# charge_pump.net
KiCad netlist of a schematic drawn in Altium Designer
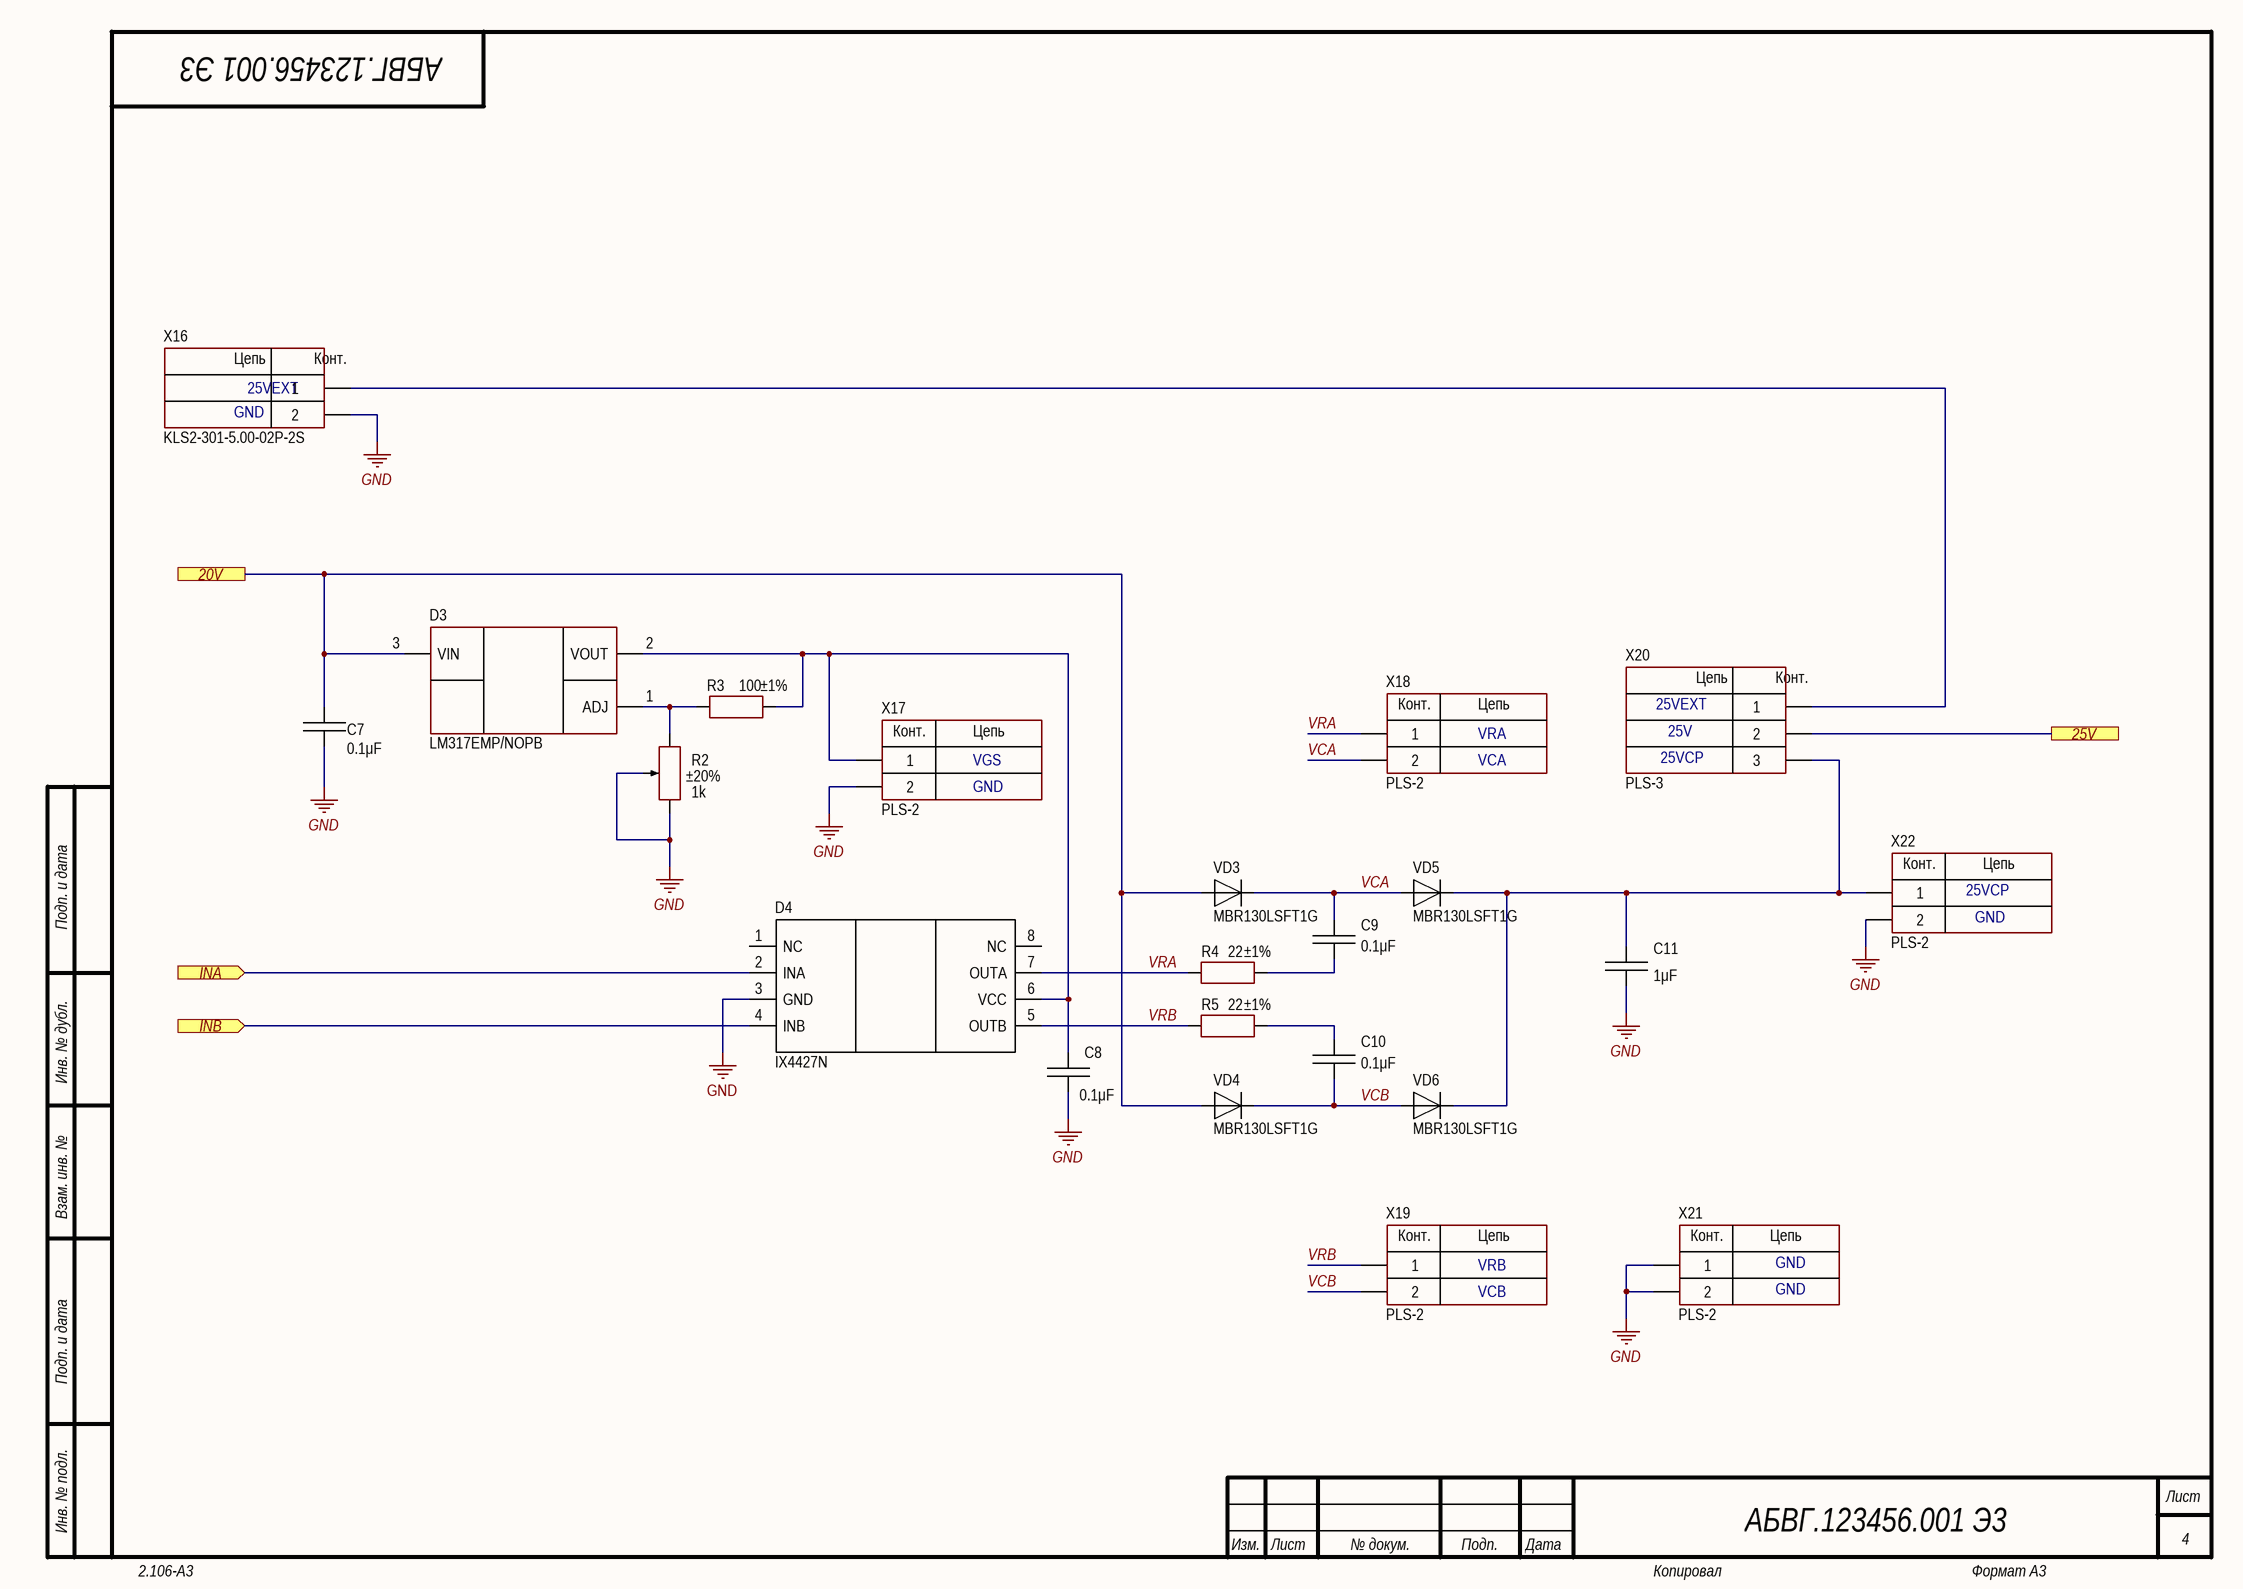
[diagram p0: charge_pump.SchDoc]

(export (version "E")
  (design (tool "Eeschema 10.0.6"))
  (components
    (comp (ref "C7")
      (value "0.1μF")
      (footprint "CAP: 1206")
      (fields
        (field (name "MANUFACTURER") "Murata Electronics")
        (field (name "PARTNUMBER") "GRM319R71H104K")
        (field (name "VALUEMANUFACTURERPARTNUMBER") "Ceramic capacitor, 0.1μF, X7R, ±10%, 50V, 1206, -55...+125°C")
      )
      (libsource (lib "capacitor") (part "Ceramic_1206"))
    )
    (comp (ref "C8")
      (value "0.1μF")
      (footprint "CAP: 1206")
      (fields
        (field (name "MANUFACTURER") "Murata Electronics")
        (field (name "PARTNUMBER") "GRM319R71H104K")
        (field (name "VALUEMANUFACTURERPARTNUMBER") "Ceramic capacitor, 0.1μF, X7R, ±10%, 50V, 1206, -55...+125°C")
      )
      (libsource (lib "capacitor") (part "Ceramic_1206"))
    )
    (comp (ref "C9")
      (value "0.1μF")
      (footprint "CAP: 1206")
      (fields
        (field (name "MANUFACTURER") "Murata Electronics")
        (field (name "PARTNUMBER") "GRM319R71H104K")
        (field (name "VALUEMANUFACTURERPARTNUMBER") "Ceramic capacitor, 0.1μF, X7R, ±10%, 50V, 1206, -55...+125°C")
      )
      (libsource (lib "capacitor") (part "Ceramic_1206"))
    )
    (comp (ref "C10")
      (value "0.1μF")
      (footprint "CAP: 1206")
      (fields
        (field (name "MANUFACTURER") "Murata Electronics")
        (field (name "PARTNUMBER") "GRM319R71H104K")
        (field (name "VALUEMANUFACTURERPARTNUMBER") "Ceramic capacitor, 0.1μF, X7R, ±10%, 50V, 1206, -55...+125°C")
      )
      (libsource (lib "capacitor") (part "Ceramic_1206"))
    )
    (comp (ref "C11")
      (value "1μF")
      (footprint "CAP: 1206")
      (fields
        (field (name "MANUFACTURER") "Murata Electronics")
        (field (name "PARTNUMBER") "GRM31MR71E105K")
        (field (name "VALUEMANUFACTURERPARTNUMBER") "Ceramic capacitor, 1μF, X7R, ±10%, 50V, 1206, -55...+125°C")
      )
      (libsource (lib "capacitor") (part "Ceramic_1206"))
    )
    (comp (ref "D3")
      (value "*")
      (footprint "SOT223")
      (description "Three-Pin Adjustable Regulator")
      (fields (field (name "MANUFACTURER") "Texas Instruments") (field (name "PARTNUMBER") "LM317EMP/NOPB"))
      (libsource (lib "ic-power-supply") (part "AMS1117-5.0"))
    )
    (comp (ref "D4")
      (value "Ixys Corporation")
      (footprint "8-SOIC")
      (description "Gate driver")
      (fields (field (name "PARTNUMBER") "IX4427N"))
      (libsource (lib "ic-gate-driver") (part "IX4427N"))
    )
    (comp (ref "R2")
      (value "1k")
      (footprint "RES: 3314G")
      (fields
        (field (name "MANUFACTURER") "Bourns")
        (field (name "PARTNUMBER") "3314G-1-103E")
        (field (name "VALUEMANUFACTURERPARTNUMBER") ", 1k, ±20%, 3314G, 0.25W, -55...+125°C")
        (field (name "TOLERANCE") "±20%")
      )
      (libsource (lib "resistor") (part "Trimmer"))
    )
    (comp (ref "R3")
      (value "100")
      (footprint "RES: 1206")
      (fields
        (field (name "MANUFACTURER") "Yageo")
        (field (name "PARTNUMBER") "RC1206JR-07100RL")
        (field (name "VALUEMANUFACTURERPARTNUMBER") "Resistor film, 100, ±1%, 1206, 0.25W, -55...+125°C")
        (field (name "TOLERANCE") "±1%")
      )
      (libsource (lib "resistor") (part "Resistor_1206"))
    )
    (comp (ref "R4")
      (value "22")
      (footprint "RES: 1206")
      (fields
        (field (name "MANUFACTURER") "Yageo")
        (field (name "PARTNUMBER") "RC1206JR-07100RL")
        (field (name "VALUEMANUFACTURERPARTNUMBER") "Resistor film, 22, ±1%, 1206, 0.25W, -55...+125°C")
        (field (name "TOLERANCE") "±1%")
      )
      (libsource (lib "resistor") (part "Resistor_1206"))
    )
    (comp (ref "R5")
      (value "22")
      (footprint "RES: 1206")
      (fields
        (field (name "MANUFACTURER") "Yageo")
        (field (name "PARTNUMBER") "RC1206JR-07100RL")
        (field (name "VALUEMANUFACTURERPARTNUMBER") "Resistor film, 22, ±1%, 1206, 0.25W, -55...+125°C")
        (field (name "TOLERANCE") "±1%")
      )
      (libsource (lib "resistor") (part "Resistor_1206"))
    )
    (comp (ref "VD3")
      (value "~")
      (footprint "DIODE: SOD123F")
      (fields
        (field (name "MANUFACTURER") "ON Semiconductor")
        (field (name "VALUEMANUFACTURERPARTNUMBER") "Single diode, 30V, 1A, 380mV, , SOD-123FL, -55…+125 C")
        (field (name "VOLTAGE") "30V")
        (field (name "PARTNUMBER") "MBR130LSFT1G")
      )
      (libsource (lib "diode") (part "Diode_single"))
    )
    (comp (ref "VD4")
      (value "~")
      (footprint "DIODE: SOD123F")
      (fields
        (field (name "MANUFACTURER") "ON Semiconductor")
        (field (name "VALUEMANUFACTURERPARTNUMBER") "Single diode, 30V, 1A, 380mV, , SOD-123FL, -55…+125 C")
        (field (name "VOLTAGE") "30V")
        (field (name "PARTNUMBER") "MBR130LSFT1G")
      )
      (libsource (lib "diode") (part "Diode_single"))
    )
    (comp (ref "VD5")
      (value "~")
      (footprint "DIODE: SOD123F")
      (fields
        (field (name "MANUFACTURER") "ON Semiconductor")
        (field (name "VALUEMANUFACTURERPARTNUMBER") "Single diode, 30V, 1A, 380mV, , SOD-123FL, -55…+125 C")
        (field (name "VOLTAGE") "30V")
        (field (name "PARTNUMBER") "MBR130LSFT1G")
      )
      (libsource (lib "diode") (part "Diode_single"))
    )
    (comp (ref "VD6")
      (value "~")
      (footprint "DIODE: SOD123F")
      (fields
        (field (name "MANUFACTURER") "ON Semiconductor")
        (field (name "VALUEMANUFACTURERPARTNUMBER") "Single diode, 30V, 1A, 380mV, , SOD-123FL, -55…+125 C")
        (field (name "VOLTAGE") "30V")
        (field (name "PARTNUMBER") "MBR130LSFT1G")
      )
      (libsource (lib "diode") (part "Diode_single"))
    )
    (comp (ref "X16")
      (value "~")
      (footprint "CON: Terminal 2p 5mm")
      (fields
        (field (name "VALUEMANUFACTURERPARTNUMBER") "Connector, 2pin, *, *, *")
        (field (name "PARTNUMBER") "KLS2-301-5.00-02P-2S")
        (field (name "COMMENTTEXT") "KLS2-301-5.00-02P-2S")
      )
      (libsource (lib "connector") (part "Terminal block 2"))
    )
    (comp (ref "X17")
      (value "~")
      (footprint "CON: PLS-2")
      (fields
        (field (name "MANUFACTURER") "Connfly")
        (field (name "VALUEMANUFACTURERPARTNUMBER") "Connector, 2pin, 2.54mm, 500VAC, 3A")
        (field (name "PARTNUMBER") "PLS-2")
        (field (name "COMMENTTEXT") "PLS-2")
      )
      (libsource (lib "connector") (part "PLS-2"))
    )
    (comp (ref "X18")
      (value "~")
      (footprint "CON: PLS-2")
      (fields
        (field (name "MANUFACTURER") "Connfly")
        (field (name "VALUEMANUFACTURERPARTNUMBER") "Connector, 2pin, 2.54mm, 500VAC, 3A")
        (field (name "PARTNUMBER") "PLS-2")
        (field (name "COMMENTTEXT") "PLS-2")
      )
      (libsource (lib "connector") (part "PLS-2"))
    )
    (comp (ref "X19")
      (value "~")
      (footprint "CON: PLS-2")
      (fields
        (field (name "MANUFACTURER") "Connfly")
        (field (name "VALUEMANUFACTURERPARTNUMBER") "Connector, 2pin, 2.54mm, 500VAC, 3A")
        (field (name "PARTNUMBER") "PLS-2")
        (field (name "COMMENTTEXT") "PLS-2")
      )
      (libsource (lib "connector") (part "PLS-2"))
    )
    (comp (ref "X20")
      (value "~")
      (footprint "CON: PLS-3")
      (fields
        (field (name "MANUFACTURER") "Connfly")
        (field (name "VALUEMANUFACTURERPARTNUMBER") "Connector, 3pin, 2.54mm, 500VAC, 3A")
        (field (name "PARTNUMBER") "PLS-3")
        (field (name "COMMENTTEXT") "PLS-3")
      )
      (libsource (lib "connector") (part "PLS-3"))
    )
    (comp (ref "X21")
      (value "~")
      (footprint "CON: PLS-2")
      (fields
        (field (name "MANUFACTURER") "Connfly")
        (field (name "VALUEMANUFACTURERPARTNUMBER") "Connector, 2pin, 2.54mm, 500VAC, 3A")
        (field (name "PARTNUMBER") "PLS-2")
        (field (name "COMMENTTEXT") "PLS-2")
      )
      (libsource (lib "connector") (part "PLS-2"))
    )
    (comp (ref "X22")
      (value "~")
      (footprint "CON: PLS-2")
      (fields
        (field (name "MANUFACTURER") "Connfly")
        (field (name "VALUEMANUFACTURERPARTNUMBER") "Connector, 2pin, 2.54mm, 500VAC, 3A")
        (field (name "PARTNUMBER") "PLS-2")
        (field (name "COMMENTTEXT") "PLS-2")
      )
      (libsource (lib "connector") (part "PLS-2"))
    )
  )
  (nets
    (net (code "1") (name "/20V") (class "Default")
      (node (ref "C7") (pin "2") (pinfunction "2_2") (pintype "passive"))
      (node (ref "D3") (pin "3") (pinfunction "VIN_3") (pintype "passive"))
      (node (ref "VD3") (pin "1") (pinfunction "1_1") (pintype "passive"))
      (node (ref "VD4") (pin "1") (pinfunction "1_1") (pintype "passive"))
    )
    (net (code "2") (name "/25V") (class "Default")
      (node (ref "X20") (pin "2") (pinfunction "2_2") (pintype "passive"))
    )
    (net (code "3") (name "/INA") (class "Default")
      (node (ref "D4") (pin "2") (pinfunction "INA_2") (pintype "passive"))
    )
    (net (code "4") (name "/INB") (class "Default")
      (node (ref "D4") (pin "4") (pinfunction "INB_4") (pintype "passive"))
    )
    (net (code "5") (name "/VCA") (class "Default")
      (node (ref "C9") (pin "2") (pinfunction "2_2") (pintype "passive"))
      (node (ref "VD3") (pin "2") (pinfunction "2_2") (pintype "passive"))
      (node (ref "VD5") (pin "1") (pinfunction "1_1") (pintype "passive"))
      (node (ref "X18") (pin "2") (pinfunction "2_2") (pintype "passive"))
    )
    (net (code "6") (name "/VCB") (class "Default")
      (node (ref "C10") (pin "1") (pinfunction "1_1") (pintype "passive"))
      (node (ref "VD4") (pin "2") (pinfunction "2_2") (pintype "passive"))
      (node (ref "VD6") (pin "1") (pinfunction "1_1") (pintype "passive"))
      (node (ref "X19") (pin "2") (pinfunction "2_2") (pintype "passive"))
    )
    (net (code "7") (name "/VRA") (class "Default")
      (node (ref "D4") (pin "7") (pinfunction "OUTA_7") (pintype "passive"))
      (node (ref "R4") (pin "2") (pinfunction "2_2") (pintype "passive"))
      (node (ref "X18") (pin "1") (pinfunction "1_1") (pintype "passive"))
    )
    (net (code "8") (name "/VRB") (class "Default")
      (node (ref "D4") (pin "5") (pinfunction "OUTB_5") (pintype "passive"))
      (node (ref "R5") (pin "2") (pinfunction "2_2") (pintype "passive"))
      (node (ref "X19") (pin "1") (pinfunction "1_1") (pintype "passive"))
    )
    (net (code "9") (name "GND") (class "Default")
      (node (ref "C11") (pin "1") (pinfunction "1_1") (pintype "passive"))
      (node (ref "C7") (pin "1") (pinfunction "1_1") (pintype "passive"))
      (node (ref "C8") (pin "1") (pinfunction "1_1") (pintype "passive"))
      (node (ref "D4") (pin "3") (pinfunction "GND_3") (pintype "passive"))
      (node (ref "R2") (pin "1") (pinfunction "1_1") (pintype "passive"))
      (node (ref "R2") (pin "2") (pinfunction "2_2") (pintype "passive"))
      (node (ref "X16") (pin "2") (pinfunction "2_2") (pintype "passive"))
      (node (ref "X17") (pin "2") (pinfunction "2_2") (pintype "passive"))
      (node (ref "X21") (pin "1") (pinfunction "1_1") (pintype "passive"))
      (node (ref "X21") (pin "2") (pinfunction "2_2") (pintype "passive"))
      (node (ref "X22") (pin "2") (pinfunction "2_2") (pintype "passive"))
    )
    (net (code "10") (name "Net-(C9-Pad1)") (class "Default")
      (node (ref "C9") (pin "1") (pinfunction "1_1") (pintype "passive"))
      (node (ref "R4") (pin "1") (pinfunction "1_1") (pintype "passive"))
    )
    (net (code "11") (name "Net-(C10-Pad2)") (class "Default")
      (node (ref "C10") (pin "2") (pinfunction "2_2") (pintype "passive"))
      (node (ref "R5") (pin "1") (pinfunction "1_1") (pintype "passive"))
    )
    (net (code "12") (name "Net-(C11-Pad2)") (class "Default")
      (node (ref "C11") (pin "2") (pinfunction "2_2") (pintype "passive"))
      (node (ref "VD5") (pin "2") (pinfunction "2_2") (pintype "passive"))
      (node (ref "VD6") (pin "2") (pinfunction "2_2") (pintype "passive"))
      (node (ref "X20") (pin "3") (pinfunction "3_3") (pintype "passive"))
      (node (ref "X22") (pin "1") (pinfunction "1_1") (pintype "passive"))
    )
    (net (code "13") (name "Net-(D3-ADJ)") (class "Default")
      (node (ref "D3") (pin "1") (pinfunction "ADJ_1") (pintype "passive"))
      (node (ref "R2") (pin "3") (pinfunction "3_3") (pintype "passive"))
      (node (ref "R3") (pin "2") (pinfunction "2_2") (pintype "passive"))
    )
    (net (code "14") (name "Net-(D3-VOUT)") (class "Default")
      (node (ref "C8") (pin "2") (pinfunction "2_2") (pintype "passive"))
      (node (ref "D3") (pin "2") (pinfunction "VOUT_2") (pintype "passive"))
      (node (ref "D4") (pin "6") (pinfunction "VCC_6") (pintype "passive"))
      (node (ref "R3") (pin "1") (pinfunction "1_1") (pintype "passive"))
      (node (ref "X17") (pin "1") (pinfunction "1_1") (pintype "passive"))
    )
    (net (code "15") (name "Net-(X16-Pad1)") (class "Default")
      (node (ref "X16") (pin "1") (pinfunction "1_1") (pintype "passive"))
      (node (ref "X20") (pin "1") (pinfunction "1_1") (pintype "passive"))
    )
    (net (code "16") (name "unconnected-(D4-NC-Pad1)") (class "Default")
      (node (ref "D4") (pin "1") (pinfunction "NC_1") (pintype "passive"))
    )
    (net (code "17") (name "unconnected-(D4-NC-Pad8)") (class "Default")
      (node (ref "D4") (pin "8") (pinfunction "NC_8") (pintype "passive"))
    )
  )
)
